# czujnik_swiatla_minibord.net
KiCad netlist of a schematic drawn in EAGLE
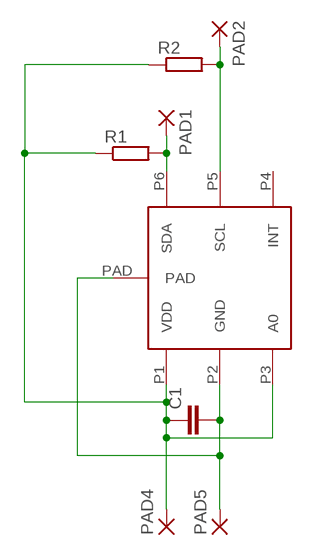
[diagram p0: schematic, sheet 1]

(export (version "E")
  (design (tool "Eeschema 10.0.6"))
  (components
    (comp (ref "C1")
      (value "C-EUC0805")
      (footprint "eagle-import:C0805")
      (libsource (lib "eagle-import") (part "C-EUC0805"))
    )
    (comp (ref "PAD1")
      (value "1,6/0,8")
      (footprint "eagle-import:1,6_0,8")
      (libsource (lib "eagle-import") (part "1,6/0,8"))
    )
    (comp (ref "PAD2")
      (value "1,6/0,8")
      (footprint "eagle-import:1,6_0,8")
      (libsource (lib "eagle-import") (part "1,6/0,8"))
    )
    (comp (ref "PAD4")
      (value "1,6/0,8")
      (footprint "eagle-import:1,6_0,8")
      (libsource (lib "eagle-import") (part "1,6/0,8"))
    )
    (comp (ref "PAD5")
      (value "1,6/0,8")
      (footprint "eagle-import:1,6_0,8")
      (libsource (lib "eagle-import") (part "1,6/0,8"))
    )
    (comp (ref "R1")
      (value "R-EU_R0805")
      (footprint "eagle-import:R0805")
      (libsource (lib "eagle-import") (part "R-EU_R0805"))
    )
    (comp (ref "R2")
      (value "R-EU_R0805")
      (footprint "eagle-import:R0805")
      (libsource (lib "eagle-import") (part "R-EU_R0805"))
    )
    (comp (ref "U$1")
      (value "MAX44006")
      (footprint "eagle-import:6OTDFN")
      (libsource (lib "eagle-import") (part "MAX44006"))
    )
  )
  (nets
    (net (code "1") (name "Net-(PAD1-P)") (class "Default")
      (node (ref "PAD1") (pin "1") (pinfunction "P_1") (pintype "passive"))
      (node (ref "R1") (pin "2") (pinfunction "2_2") (pintype "passive"))
      (node (ref "U$1") (pin "P6") (pinfunction "SDA_P6") (pintype "bidirectional"))
    )
    (net (code "2") (name "Net-(PAD2-P)") (class "Default")
      (node (ref "PAD2") (pin "1") (pinfunction "P_1") (pintype "passive"))
      (node (ref "R2") (pin "2") (pinfunction "2_2") (pintype "passive"))
      (node (ref "U$1") (pin "P5") (pinfunction "SCL_P5") (pintype "bidirectional"))
    )
    (net (code "3") (name "Net-(PAD4-P)") (class "Default")
      (node (ref "C1") (pin "1") (pinfunction "1_1") (pintype "passive"))
      (node (ref "PAD4") (pin "1") (pinfunction "P_1") (pintype "passive"))
      (node (ref "R1") (pin "1") (pinfunction "1_1") (pintype "passive"))
      (node (ref "R2") (pin "1") (pinfunction "1_1") (pintype "passive"))
      (node (ref "U$1") (pin "P1") (pinfunction "VDD_P1") (pintype "bidirectional"))
      (node (ref "U$1") (pin "P3") (pinfunction "A0_P3") (pintype "bidirectional"))
    )
    (net (code "4") (name "Net-(PAD5-P)") (class "Default")
      (node (ref "C1") (pin "2") (pinfunction "2_2") (pintype "passive"))
      (node (ref "PAD5") (pin "1") (pinfunction "P_1") (pintype "passive"))
      (node (ref "U$1") (pin "P2") (pinfunction "GND_P2") (pintype "bidirectional"))
      (node (ref "U$1") (pin "PAD") (pinfunction "PAD_PAD") (pintype "bidirectional"))
    )
    (net (code "5") (name "unconnected-(U$1-INT-PadP4)") (class "Default")
      (node (ref "U$1") (pin "P4") (pinfunction "INT_P4") (pintype "bidirectional"))
    )
  )
)
